# MB_ANALOG.net
KiCad netlist of a schematic drawn in Altium Designer
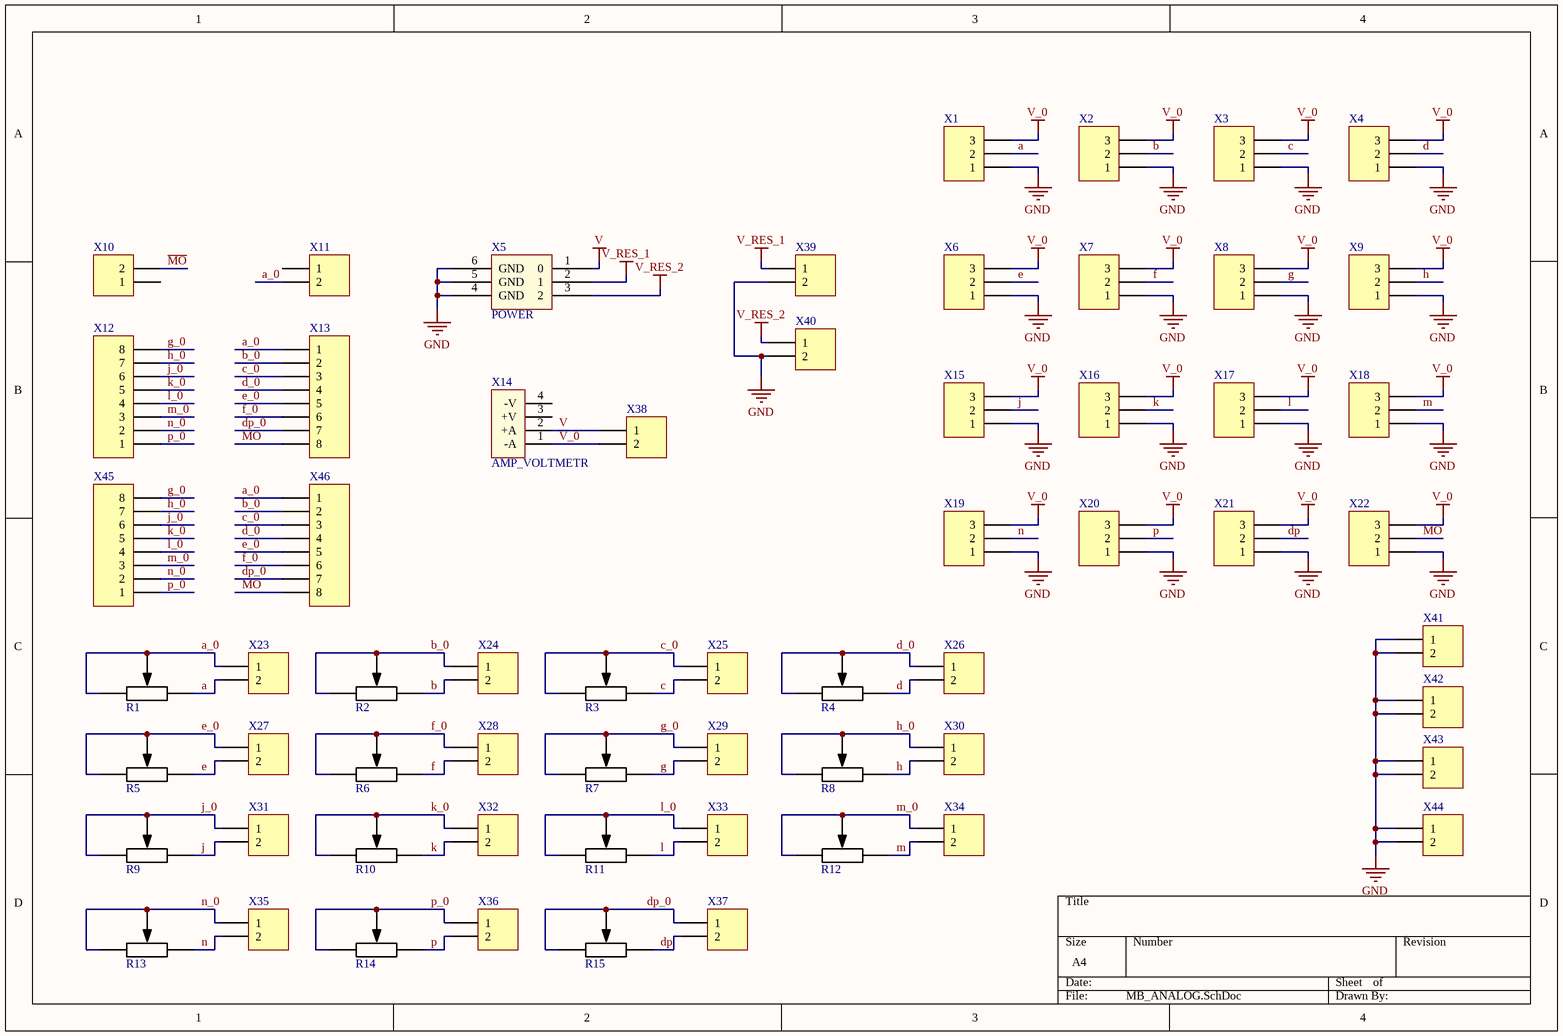
[diagram p0: MB_ANALOG.SchDoc]

(export (version "E")
  (design (tool "Eeschema 10.0.6"))
  (components
    (comp (ref "R1")
      (value "RES 3266W")
      (footprint "RES 3266W")
      (libsource (lib "msp_SchLib") (part "RES 3266W"))
    )
    (comp (ref "R2")
      (value "RES 3266W")
      (footprint "RES 3266W")
      (libsource (lib "msp_SchLib") (part "RES 3266W"))
    )
    (comp (ref "R3")
      (value "RES 3266W")
      (footprint "RES 3266W")
      (libsource (lib "msp_SchLib") (part "RES 3266W"))
    )
    (comp (ref "R4")
      (value "RES 3266W")
      (footprint "RES 3266W")
      (libsource (lib "msp_SchLib") (part "RES 3266W"))
    )
    (comp (ref "R5")
      (value "RES 3266W")
      (footprint "RES 3266W")
      (libsource (lib "msp_SchLib") (part "RES 3266W"))
    )
    (comp (ref "R6")
      (value "RES 3266W")
      (footprint "RES 3266W")
      (libsource (lib "msp_SchLib") (part "RES 3266W"))
    )
    (comp (ref "R7")
      (value "RES 3266W")
      (footprint "RES 3266W")
      (libsource (lib "msp_SchLib") (part "RES 3266W"))
    )
    (comp (ref "R8")
      (value "RES 3266W")
      (footprint "RES 3266W")
      (libsource (lib "msp_SchLib") (part "RES 3266W"))
    )
    (comp (ref "R9")
      (value "RES 3266W")
      (footprint "RES 3266W")
      (libsource (lib "msp_SchLib") (part "RES 3266W"))
    )
    (comp (ref "R10")
      (value "RES 3266W")
      (footprint "RES 3266W")
      (libsource (lib "msp_SchLib") (part "RES 3266W"))
    )
    (comp (ref "R11")
      (value "RES 3266W")
      (footprint "RES 3266W")
      (libsource (lib "msp_SchLib") (part "RES 3266W"))
    )
    (comp (ref "R12")
      (value "RES 3266W")
      (footprint "RES 3266W")
      (libsource (lib "msp_SchLib") (part "RES 3266W"))
    )
    (comp (ref "R13")
      (value "RES 3266W")
      (footprint "RES 3266W")
      (libsource (lib "msp_SchLib") (part "RES 3266W"))
    )
    (comp (ref "R14")
      (value "RES 3266W")
      (footprint "RES 3266W")
      (libsource (lib "msp_SchLib") (part "RES 3266W"))
    )
    (comp (ref "R15")
      (value "RES 3266W")
      (footprint "RES 3266W")
      (libsource (lib "msp_SchLib") (part "RES 3266W"))
    )
    (comp (ref "X1")
      (value "Header 3")
      (footprint "HDR1X3")
      (description "Header, 3-Pin")
      (fields (field (name "PUBLISHER") "Altium Limited"))
      (libsource (lib "Miscellaneous Connectors") (part "Header 3"))
    )
    (comp (ref "X2")
      (value "Header 3")
      (footprint "HDR1X3")
      (description "Header, 3-Pin")
      (fields (field (name "PUBLISHER") "Altium Limited"))
      (libsource (lib "Miscellaneous Connectors") (part "Header 3"))
    )
    (comp (ref "X3")
      (value "Header 3")
      (footprint "HDR1X3")
      (description "Header, 3-Pin")
      (fields (field (name "PUBLISHER") "Altium Limited"))
      (libsource (lib "Miscellaneous Connectors") (part "Header 3"))
    )
    (comp (ref "X4")
      (value "Header 3")
      (footprint "HDR1X3")
      (description "Header, 3-Pin")
      (fields (field (name "PUBLISHER") "Altium Limited"))
      (libsource (lib "Miscellaneous Connectors") (part "Header 3"))
    )
    (comp (ref "X5") (value "POWER") (footprint "POWER") (libsource (lib "msp_SchLib") (part "POWER")))
    (comp (ref "X6")
      (value "Header 3")
      (footprint "HDR1X3")
      (description "Header, 3-Pin")
      (fields (field (name "PUBLISHER") "Altium Limited"))
      (libsource (lib "Miscellaneous Connectors") (part "Header 3"))
    )
    (comp (ref "X7")
      (value "Header 3")
      (footprint "HDR1X3")
      (description "Header, 3-Pin")
      (fields (field (name "PUBLISHER") "Altium Limited"))
      (libsource (lib "Miscellaneous Connectors") (part "Header 3"))
    )
    (comp (ref "X8")
      (value "Header 3")
      (footprint "HDR1X3")
      (description "Header, 3-Pin")
      (fields (field (name "PUBLISHER") "Altium Limited"))
      (libsource (lib "Miscellaneous Connectors") (part "Header 3"))
    )
    (comp (ref "X9")
      (value "Header 3")
      (footprint "HDR1X3")
      (description "Header, 3-Pin")
      (fields (field (name "PUBLISHER") "Altium Limited"))
      (libsource (lib "Miscellaneous Connectors") (part "Header 3"))
    )
    (comp (ref "X10")
      (value "Header 2")
      (footprint "HDR1X2")
      (description "Header, 2-Pin")
      (fields (field (name "PUBLISHER") "Altium Limited"))
      (libsource (lib "") (part "Header 2_1"))
    )
    (comp (ref "X11")
      (value "Header 2")
      (footprint "HDR1X2")
      (description "Header, 2-Pin")
      (fields (field (name "PUBLISHER") "Altium Limited"))
      (libsource (lib "Miscellaneous Connectors") (part "Header 2"))
    )
    (comp (ref "X12")
      (value "Header 8")
      (footprint "HDR1X8")
      (description "Header, 8-Pin")
      (fields (field (name "PUBLISHER") "Altium Limited"))
      (libsource (lib "Miscellaneous Connectors") (part "Header 8"))
    )
    (comp (ref "X13")
      (value "Header 8")
      (footprint "HDR1X8")
      (description "Header, 8-Pin")
      (fields (field (name "PUBLISHER") "Altium Limited"))
      (libsource (lib "") (part "Header 8_1"))
    )
    (comp (ref "X14")
      (value "AMP_VOLTMETR")
      (footprint "AMP_VOLTMETR")
      (libsource (lib "msp_SchLib") (part "AMP_VOLTMETR"))
    )
    (comp (ref "X15")
      (value "Header 3")
      (footprint "HDR1X3")
      (description "Header, 3-Pin")
      (fields (field (name "PUBLISHER") "Altium Limited"))
      (libsource (lib "Miscellaneous Connectors") (part "Header 3"))
    )
    (comp (ref "X16")
      (value "Header 3")
      (footprint "HDR1X3")
      (description "Header, 3-Pin")
      (fields (field (name "PUBLISHER") "Altium Limited"))
      (libsource (lib "Miscellaneous Connectors") (part "Header 3"))
    )
    (comp (ref "X17")
      (value "Header 3")
      (footprint "HDR1X3")
      (description "Header, 3-Pin")
      (fields (field (name "PUBLISHER") "Altium Limited"))
      (libsource (lib "Miscellaneous Connectors") (part "Header 3"))
    )
    (comp (ref "X18")
      (value "Header 3")
      (footprint "HDR1X3")
      (description "Header, 3-Pin")
      (fields (field (name "PUBLISHER") "Altium Limited"))
      (libsource (lib "Miscellaneous Connectors") (part "Header 3"))
    )
    (comp (ref "X19")
      (value "Header 3")
      (footprint "HDR1X3")
      (description "Header, 3-Pin")
      (fields (field (name "PUBLISHER") "Altium Limited"))
      (libsource (lib "Miscellaneous Connectors") (part "Header 3"))
    )
    (comp (ref "X20")
      (value "Header 3")
      (footprint "HDR1X3")
      (description "Header, 3-Pin")
      (fields (field (name "PUBLISHER") "Altium Limited"))
      (libsource (lib "Miscellaneous Connectors") (part "Header 3"))
    )
    (comp (ref "X21")
      (value "Header 3")
      (footprint "HDR1X3")
      (description "Header, 3-Pin")
      (fields (field (name "PUBLISHER") "Altium Limited"))
      (libsource (lib "Miscellaneous Connectors") (part "Header 3"))
    )
    (comp (ref "X22")
      (value "Header 3")
      (footprint "HDR1X3")
      (description "Header, 3-Pin")
      (fields (field (name "PUBLISHER") "Altium Limited"))
      (libsource (lib "Miscellaneous Connectors") (part "Header 3"))
    )
    (comp (ref "X23")
      (value "Header 2")
      (footprint "HDR1X2")
      (description "Header, 2-Pin")
      (fields (field (name "PUBLISHER") "Altium Limited"))
      (libsource (lib "Miscellaneous Connectors") (part "Header 2"))
    )
    (comp (ref "X24")
      (value "Header 2")
      (footprint "HDR1X2")
      (description "Header, 2-Pin")
      (fields (field (name "PUBLISHER") "Altium Limited"))
      (libsource (lib "Miscellaneous Connectors") (part "Header 2"))
    )
    (comp (ref "X25")
      (value "Header 2")
      (footprint "HDR1X2")
      (description "Header, 2-Pin")
      (fields (field (name "PUBLISHER") "Altium Limited"))
      (libsource (lib "Miscellaneous Connectors") (part "Header 2"))
    )
    (comp (ref "X26")
      (value "Header 2")
      (footprint "HDR1X2")
      (description "Header, 2-Pin")
      (fields (field (name "PUBLISHER") "Altium Limited"))
      (libsource (lib "Miscellaneous Connectors") (part "Header 2"))
    )
    (comp (ref "X27")
      (value "Header 2")
      (footprint "HDR1X2")
      (description "Header, 2-Pin")
      (fields (field (name "PUBLISHER") "Altium Limited"))
      (libsource (lib "Miscellaneous Connectors") (part "Header 2"))
    )
    (comp (ref "X28")
      (value "Header 2")
      (footprint "HDR1X2")
      (description "Header, 2-Pin")
      (fields (field (name "PUBLISHER") "Altium Limited"))
      (libsource (lib "Miscellaneous Connectors") (part "Header 2"))
    )
    (comp (ref "X29")
      (value "Header 2")
      (footprint "HDR1X2")
      (description "Header, 2-Pin")
      (fields (field (name "PUBLISHER") "Altium Limited"))
      (libsource (lib "Miscellaneous Connectors") (part "Header 2"))
    )
    (comp (ref "X30")
      (value "Header 2")
      (footprint "HDR1X2")
      (description "Header, 2-Pin")
      (fields (field (name "PUBLISHER") "Altium Limited"))
      (libsource (lib "Miscellaneous Connectors") (part "Header 2"))
    )
    (comp (ref "X31")
      (value "Header 2")
      (footprint "HDR1X2")
      (description "Header, 2-Pin")
      (fields (field (name "PUBLISHER") "Altium Limited"))
      (libsource (lib "Miscellaneous Connectors") (part "Header 2"))
    )
    (comp (ref "X32")
      (value "Header 2")
      (footprint "HDR1X2")
      (description "Header, 2-Pin")
      (fields (field (name "PUBLISHER") "Altium Limited"))
      (libsource (lib "Miscellaneous Connectors") (part "Header 2"))
    )
    (comp (ref "X33")
      (value "Header 2")
      (footprint "HDR1X2")
      (description "Header, 2-Pin")
      (fields (field (name "PUBLISHER") "Altium Limited"))
      (libsource (lib "Miscellaneous Connectors") (part "Header 2"))
    )
    (comp (ref "X34")
      (value "Header 2")
      (footprint "HDR1X2")
      (description "Header, 2-Pin")
      (fields (field (name "PUBLISHER") "Altium Limited"))
      (libsource (lib "Miscellaneous Connectors") (part "Header 2"))
    )
    (comp (ref "X35")
      (value "Header 2")
      (footprint "HDR1X2")
      (description "Header, 2-Pin")
      (fields (field (name "PUBLISHER") "Altium Limited"))
      (libsource (lib "Miscellaneous Connectors") (part "Header 2"))
    )
    (comp (ref "X36")
      (value "Header 2")
      (footprint "HDR1X2")
      (description "Header, 2-Pin")
      (fields (field (name "PUBLISHER") "Altium Limited"))
      (libsource (lib "Miscellaneous Connectors") (part "Header 2"))
    )
    (comp (ref "X37")
      (value "Header 2")
      (footprint "HDR1X2")
      (description "Header, 2-Pin")
      (fields (field (name "PUBLISHER") "Altium Limited"))
      (libsource (lib "Miscellaneous Connectors") (part "Header 2"))
    )
    (comp (ref "X38")
      (value "Header 2")
      (footprint "HDR1X2")
      (description "Header, 2-Pin")
      (fields (field (name "PUBLISHER") "Altium Limited"))
      (libsource (lib "Miscellaneous Connectors") (part "Header 2"))
    )
    (comp (ref "X39")
      (value "Header 2")
      (footprint "HDR1X2")
      (description "Header, 2-Pin")
      (fields (field (name "PUBLISHER") "Altium Limited"))
      (libsource (lib "Miscellaneous Connectors") (part "Header 2"))
    )
    (comp (ref "X40")
      (value "Header 2")
      (footprint "HDR1X2")
      (description "Header, 2-Pin")
      (fields (field (name "PUBLISHER") "Altium Limited"))
      (libsource (lib "Miscellaneous Connectors") (part "Header 2"))
    )
    (comp (ref "X41")
      (value "Header 2")
      (footprint "HDR1X2")
      (description "Header, 2-Pin")
      (fields (field (name "PUBLISHER") "Altium Limited"))
      (libsource (lib "Miscellaneous Connectors") (part "Header 2"))
    )
    (comp (ref "X42")
      (value "Header 2")
      (footprint "HDR1X2")
      (description "Header, 2-Pin")
      (fields (field (name "PUBLISHER") "Altium Limited"))
      (libsource (lib "Miscellaneous Connectors") (part "Header 2"))
    )
    (comp (ref "X43")
      (value "Header 2")
      (footprint "HDR1X2")
      (description "Header, 2-Pin")
      (fields (field (name "PUBLISHER") "Altium Limited"))
      (libsource (lib "Miscellaneous Connectors") (part "Header 2"))
    )
    (comp (ref "X44")
      (value "Header 2")
      (footprint "HDR1X2")
      (description "Header, 2-Pin")
      (fields (field (name "PUBLISHER") "Altium Limited"))
      (libsource (lib "Miscellaneous Connectors") (part "Header 2"))
    )
    (comp (ref "X45")
      (value "Header 8")
      (footprint "HDR1X8")
      (description "Header, 8-Pin")
      (fields (field (name "PUBLISHER") "Altium Limited"))
      (libsource (lib "Miscellaneous Connectors") (part "Header 8"))
    )
    (comp (ref "X46")
      (value "Header 8")
      (footprint "HDR1X8")
      (description "Header, 8-Pin")
      (fields (field (name "PUBLISHER") "Altium Limited"))
      (libsource (lib "") (part "Header 8_1"))
    )
  )
  (nets
    (net (code "1") (name "/a") (class "Default")
      (node (ref "R1") (pin "3") (pinfunction "3_3") (pintype "passive"))
      (node (ref "X1") (pin "2") (pinfunction "2_2") (pintype "passive"))
      (node (ref "X23") (pin "2") (pinfunction "2_2") (pintype "passive"))
    )
    (net (code "2") (name "/a_0") (class "Default")
      (node (ref "R1") (pin "1") (pinfunction "1_1") (pintype "passive"))
      (node (ref "R1") (pin "2") (pinfunction "2_2") (pintype "passive"))
      (node (ref "X11") (pin "2") (pinfunction "2_2") (pintype "passive"))
      (node (ref "X13") (pin "1") (pinfunction "1_1") (pintype "passive"))
      (node (ref "X23") (pin "1") (pinfunction "1_1") (pintype "passive"))
      (node (ref "X46") (pin "1") (pinfunction "1_1") (pintype "passive"))
    )
    (net (code "3") (name "/b") (class "Default")
      (node (ref "R2") (pin "3") (pinfunction "3_3") (pintype "passive"))
      (node (ref "X2") (pin "2") (pinfunction "2_2") (pintype "passive"))
      (node (ref "X24") (pin "2") (pinfunction "2_2") (pintype "passive"))
    )
    (net (code "4") (name "/b_0") (class "Default")
      (node (ref "R2") (pin "1") (pinfunction "1_1") (pintype "passive"))
      (node (ref "R2") (pin "2") (pinfunction "2_2") (pintype "passive"))
      (node (ref "X13") (pin "2") (pinfunction "2_2") (pintype "passive"))
      (node (ref "X24") (pin "1") (pinfunction "1_1") (pintype "passive"))
      (node (ref "X46") (pin "2") (pinfunction "2_2") (pintype "passive"))
    )
    (net (code "5") (name "/c") (class "Default")
      (node (ref "R3") (pin "3") (pinfunction "3_3") (pintype "passive"))
      (node (ref "X25") (pin "2") (pinfunction "2_2") (pintype "passive"))
      (node (ref "X3") (pin "2") (pinfunction "2_2") (pintype "passive"))
    )
    (net (code "6") (name "/c_0") (class "Default")
      (node (ref "R3") (pin "1") (pinfunction "1_1") (pintype "passive"))
      (node (ref "R3") (pin "2") (pinfunction "2_2") (pintype "passive"))
      (node (ref "X13") (pin "3") (pinfunction "3_3") (pintype "passive"))
      (node (ref "X25") (pin "1") (pinfunction "1_1") (pintype "passive"))
      (node (ref "X46") (pin "3") (pinfunction "3_3") (pintype "passive"))
    )
    (net (code "7") (name "/d") (class "Default")
      (node (ref "R4") (pin "3") (pinfunction "3_3") (pintype "passive"))
      (node (ref "X26") (pin "2") (pinfunction "2_2") (pintype "passive"))
      (node (ref "X4") (pin "2") (pinfunction "2_2") (pintype "passive"))
    )
    (net (code "8") (name "/d_0") (class "Default")
      (node (ref "R4") (pin "1") (pinfunction "1_1") (pintype "passive"))
      (node (ref "R4") (pin "2") (pinfunction "2_2") (pintype "passive"))
      (node (ref "X13") (pin "4") (pinfunction "4_4") (pintype "passive"))
      (node (ref "X26") (pin "1") (pinfunction "1_1") (pintype "passive"))
      (node (ref "X46") (pin "4") (pinfunction "4_4") (pintype "passive"))
    )
    (net (code "9") (name "/dp") (class "Default")
      (node (ref "R15") (pin "3") (pinfunction "3_3") (pintype "passive"))
      (node (ref "X21") (pin "2") (pinfunction "2_2") (pintype "passive"))
      (node (ref "X37") (pin "2") (pinfunction "2_2") (pintype "passive"))
    )
    (net (code "10") (name "/dp_0") (class "Default")
      (node (ref "R15") (pin "1") (pinfunction "1_1") (pintype "passive"))
      (node (ref "R15") (pin "2") (pinfunction "2_2") (pintype "passive"))
      (node (ref "X13") (pin "7") (pinfunction "7_7") (pintype "passive"))
      (node (ref "X37") (pin "1") (pinfunction "1_1") (pintype "passive"))
      (node (ref "X46") (pin "7") (pinfunction "7_7") (pintype "passive"))
    )
    (net (code "11") (name "/e") (class "Default")
      (node (ref "R5") (pin "3") (pinfunction "3_3") (pintype "passive"))
      (node (ref "X27") (pin "2") (pinfunction "2_2") (pintype "passive"))
      (node (ref "X6") (pin "2") (pinfunction "2_2") (pintype "passive"))
    )
    (net (code "12") (name "/e_0") (class "Default")
      (node (ref "R5") (pin "1") (pinfunction "1_1") (pintype "passive"))
      (node (ref "R5") (pin "2") (pinfunction "2_2") (pintype "passive"))
      (node (ref "X13") (pin "5") (pinfunction "5_5") (pintype "passive"))
      (node (ref "X27") (pin "1") (pinfunction "1_1") (pintype "passive"))
      (node (ref "X46") (pin "5") (pinfunction "5_5") (pintype "passive"))
    )
    (net (code "13") (name "/f") (class "Default")
      (node (ref "R6") (pin "3") (pinfunction "3_3") (pintype "passive"))
      (node (ref "X28") (pin "2") (pinfunction "2_2") (pintype "passive"))
      (node (ref "X7") (pin "2") (pinfunction "2_2") (pintype "passive"))
    )
    (net (code "14") (name "/f_0") (class "Default")
      (node (ref "R6") (pin "1") (pinfunction "1_1") (pintype "passive"))
      (node (ref "R6") (pin "2") (pinfunction "2_2") (pintype "passive"))
      (node (ref "X13") (pin "6") (pinfunction "6_6") (pintype "passive"))
      (node (ref "X28") (pin "1") (pinfunction "1_1") (pintype "passive"))
      (node (ref "X46") (pin "6") (pinfunction "6_6") (pintype "passive"))
    )
    (net (code "15") (name "/g") (class "Default")
      (node (ref "R7") (pin "3") (pinfunction "3_3") (pintype "passive"))
      (node (ref "X29") (pin "2") (pinfunction "2_2") (pintype "passive"))
      (node (ref "X8") (pin "2") (pinfunction "2_2") (pintype "passive"))
    )
    (net (code "16") (name "/g_0") (class "Default")
      (node (ref "R7") (pin "1") (pinfunction "1_1") (pintype "passive"))
      (node (ref "R7") (pin "2") (pinfunction "2_2") (pintype "passive"))
      (node (ref "X12") (pin "8") (pinfunction "8_8") (pintype "passive"))
      (node (ref "X29") (pin "1") (pinfunction "1_1") (pintype "passive"))
      (node (ref "X45") (pin "8") (pinfunction "8_8") (pintype "passive"))
    )
    (net (code "17") (name "/h") (class "Default")
      (node (ref "R8") (pin "3") (pinfunction "3_3") (pintype "passive"))
      (node (ref "X30") (pin "2") (pinfunction "2_2") (pintype "passive"))
      (node (ref "X9") (pin "2") (pinfunction "2_2") (pintype "passive"))
    )
    (net (code "18") (name "/h_0") (class "Default")
      (node (ref "R8") (pin "1") (pinfunction "1_1") (pintype "passive"))
      (node (ref "R8") (pin "2") (pinfunction "2_2") (pintype "passive"))
      (node (ref "X12") (pin "7") (pinfunction "7_7") (pintype "passive"))
      (node (ref "X30") (pin "1") (pinfunction "1_1") (pintype "passive"))
      (node (ref "X45") (pin "7") (pinfunction "7_7") (pintype "passive"))
    )
    (net (code "19") (name "/j") (class "Default")
      (node (ref "R9") (pin "3") (pinfunction "3_3") (pintype "passive"))
      (node (ref "X15") (pin "2") (pinfunction "2_2") (pintype "passive"))
      (node (ref "X31") (pin "2") (pinfunction "2_2") (pintype "passive"))
    )
    (net (code "20") (name "/j_0") (class "Default")
      (node (ref "R9") (pin "1") (pinfunction "1_1") (pintype "passive"))
      (node (ref "R9") (pin "2") (pinfunction "2_2") (pintype "passive"))
      (node (ref "X12") (pin "6") (pinfunction "6_6") (pintype "passive"))
      (node (ref "X31") (pin "1") (pinfunction "1_1") (pintype "passive"))
      (node (ref "X45") (pin "6") (pinfunction "6_6") (pintype "passive"))
    )
    (net (code "21") (name "/k") (class "Default")
      (node (ref "R10") (pin "3") (pinfunction "3_3") (pintype "passive"))
      (node (ref "X16") (pin "2") (pinfunction "2_2") (pintype "passive"))
      (node (ref "X32") (pin "2") (pinfunction "2_2") (pintype "passive"))
    )
    (net (code "22") (name "/k_0") (class "Default")
      (node (ref "R10") (pin "1") (pinfunction "1_1") (pintype "passive"))
      (node (ref "R10") (pin "2") (pinfunction "2_2") (pintype "passive"))
      (node (ref "X12") (pin "5") (pinfunction "5_5") (pintype "passive"))
      (node (ref "X32") (pin "1") (pinfunction "1_1") (pintype "passive"))
      (node (ref "X45") (pin "5") (pinfunction "5_5") (pintype "passive"))
    )
    (net (code "23") (name "/l") (class "Default")
      (node (ref "R11") (pin "3") (pinfunction "3_3") (pintype "passive"))
      (node (ref "X17") (pin "2") (pinfunction "2_2") (pintype "passive"))
      (node (ref "X33") (pin "2") (pinfunction "2_2") (pintype "passive"))
    )
    (net (code "24") (name "/l_0") (class "Default")
      (node (ref "R11") (pin "1") (pinfunction "1_1") (pintype "passive"))
      (node (ref "R11") (pin "2") (pinfunction "2_2") (pintype "passive"))
      (node (ref "X12") (pin "4") (pinfunction "4_4") (pintype "passive"))
      (node (ref "X33") (pin "1") (pinfunction "1_1") (pintype "passive"))
      (node (ref "X45") (pin "4") (pinfunction "4_4") (pintype "passive"))
    )
    (net (code "25") (name "/m") (class "Default")
      (node (ref "R12") (pin "3") (pinfunction "3_3") (pintype "passive"))
      (node (ref "X18") (pin "2") (pinfunction "2_2") (pintype "passive"))
      (node (ref "X34") (pin "2") (pinfunction "2_2") (pintype "passive"))
    )
    (net (code "26") (name "/m_0") (class "Default")
      (node (ref "R12") (pin "1") (pinfunction "1_1") (pintype "passive"))
      (node (ref "R12") (pin "2") (pinfunction "2_2") (pintype "passive"))
      (node (ref "X12") (pin "3") (pinfunction "3_3") (pintype "passive"))
      (node (ref "X34") (pin "1") (pinfunction "1_1") (pintype "passive"))
      (node (ref "X45") (pin "3") (pinfunction "3_3") (pintype "passive"))
    )
    (net (code "27") (name "/n") (class "Default")
      (node (ref "R13") (pin "3") (pinfunction "3_3") (pintype "passive"))
      (node (ref "X19") (pin "2") (pinfunction "2_2") (pintype "passive"))
      (node (ref "X35") (pin "2") (pinfunction "2_2") (pintype "passive"))
    )
    (net (code "28") (name "/n_0") (class "Default")
      (node (ref "R13") (pin "1") (pinfunction "1_1") (pintype "passive"))
      (node (ref "R13") (pin "2") (pinfunction "2_2") (pintype "passive"))
      (node (ref "X12") (pin "2") (pinfunction "2_2") (pintype "passive"))
      (node (ref "X35") (pin "1") (pinfunction "1_1") (pintype "passive"))
      (node (ref "X45") (pin "2") (pinfunction "2_2") (pintype "passive"))
    )
    (net (code "29") (name "/p") (class "Default")
      (node (ref "R14") (pin "3") (pinfunction "3_3") (pintype "passive"))
      (node (ref "X20") (pin "2") (pinfunction "2_2") (pintype "passive"))
      (node (ref "X36") (pin "2") (pinfunction "2_2") (pintype "passive"))
    )
    (net (code "30") (name "/p_0") (class "Default")
      (node (ref "R14") (pin "1") (pinfunction "1_1") (pintype "passive"))
      (node (ref "R14") (pin "2") (pinfunction "2_2") (pintype "passive"))
      (node (ref "X12") (pin "1") (pinfunction "1_1") (pintype "passive"))
      (node (ref "X36") (pin "1") (pinfunction "1_1") (pintype "passive"))
      (node (ref "X45") (pin "1") (pinfunction "1_1") (pintype "passive"))
    )
    (net (code "31") (name "/~{MO}") (class "Default")
      (node (ref "X10") (pin "2") (pinfunction "2_2") (pintype "passive"))
      (node (ref "X13") (pin "8") (pinfunction "8_8") (pintype "passive"))
      (node (ref "X22") (pin "2") (pinfunction "2_2") (pintype "passive"))
      (node (ref "X46") (pin "8") (pinfunction "8_8") (pintype "passive"))
    )
    (net (code "32") (name "GND") (class "Default")
      (node (ref "X1") (pin "1") (pinfunction "1_1") (pintype "passive"))
      (node (ref "X15") (pin "1") (pinfunction "1_1") (pintype "passive"))
      (node (ref "X16") (pin "1") (pinfunction "1_1") (pintype "passive"))
      (node (ref "X17") (pin "1") (pinfunction "1_1") (pintype "passive"))
      (node (ref "X18") (pin "1") (pinfunction "1_1") (pintype "passive"))
      (node (ref "X19") (pin "1") (pinfunction "1_1") (pintype "passive"))
      (node (ref "X2") (pin "1") (pinfunction "1_1") (pintype "passive"))
      (node (ref "X20") (pin "1") (pinfunction "1_1") (pintype "passive"))
      (node (ref "X21") (pin "1") (pinfunction "1_1") (pintype "passive"))
      (node (ref "X22") (pin "1") (pinfunction "1_1") (pintype "passive"))
      (node (ref "X3") (pin "1") (pinfunction "1_1") (pintype "passive"))
      (node (ref "X39") (pin "2") (pinfunction "2_2") (pintype "passive"))
      (node (ref "X4") (pin "1") (pinfunction "1_1") (pintype "passive"))
      (node (ref "X40") (pin "2") (pinfunction "2_2") (pintype "passive"))
      (node (ref "X41") (pin "1") (pinfunction "1_1") (pintype "passive"))
      (node (ref "X41") (pin "2") (pinfunction "2_2") (pintype "passive"))
      (node (ref "X42") (pin "1") (pinfunction "1_1") (pintype "passive"))
      (node (ref "X42") (pin "2") (pinfunction "2_2") (pintype "passive"))
      (node (ref "X43") (pin "1") (pinfunction "1_1") (pintype "passive"))
      (node (ref "X43") (pin "2") (pinfunction "2_2") (pintype "passive"))
      (node (ref "X44") (pin "1") (pinfunction "1_1") (pintype "passive"))
      (node (ref "X44") (pin "2") (pinfunction "2_2") (pintype "passive"))
      (node (ref "X5") (pin "4") (pinfunction "GND_4") (pintype "passive"))
      (node (ref "X5") (pin "5") (pinfunction "GND_5") (pintype "passive"))
      (node (ref "X5") (pin "6") (pinfunction "GND_6") (pintype "passive"))
      (node (ref "X6") (pin "1") (pinfunction "1_1") (pintype "passive"))
      (node (ref "X7") (pin "1") (pinfunction "1_1") (pintype "passive"))
      (node (ref "X8") (pin "1") (pinfunction "1_1") (pintype "passive"))
      (node (ref "X9") (pin "1") (pinfunction "1_1") (pintype "passive"))
    )
    (net (code "33") (name "V") (class "Default")
      (node (ref "X14") (pin "2") (pinfunction "+A_2") (pintype "passive"))
      (node (ref "X38") (pin "1") (pinfunction "1_1") (pintype "passive"))
      (node (ref "X5") (pin "1") (pinfunction "0_1") (pintype "passive"))
    )
    (net (code "34") (name "V_0") (class "Default")
      (node (ref "X1") (pin "3") (pinfunction "3_3") (pintype "passive"))
      (node (ref "X14") (pin "1") (pinfunction "-A_1") (pintype "passive"))
      (node (ref "X15") (pin "3") (pinfunction "3_3") (pintype "passive"))
      (node (ref "X16") (pin "3") (pinfunction "3_3") (pintype "passive"))
      (node (ref "X17") (pin "3") (pinfunction "3_3") (pintype "passive"))
      (node (ref "X18") (pin "3") (pinfunction "3_3") (pintype "passive"))
      (node (ref "X19") (pin "3") (pinfunction "3_3") (pintype "passive"))
      (node (ref "X2") (pin "3") (pinfunction "3_3") (pintype "passive"))
      (node (ref "X20") (pin "3") (pinfunction "3_3") (pintype "passive"))
      (node (ref "X21") (pin "3") (pinfunction "3_3") (pintype "passive"))
      (node (ref "X22") (pin "3") (pinfunction "3_3") (pintype "passive"))
      (node (ref "X3") (pin "3") (pinfunction "3_3") (pintype "passive"))
      (node (ref "X38") (pin "2") (pinfunction "2_2") (pintype "passive"))
      (node (ref "X4") (pin "3") (pinfunction "3_3") (pintype "passive"))
      (node (ref "X6") (pin "3") (pinfunction "3_3") (pintype "passive"))
      (node (ref "X7") (pin "3") (pinfunction "3_3") (pintype "passive"))
      (node (ref "X8") (pin "3") (pinfunction "3_3") (pintype "passive"))
      (node (ref "X9") (pin "3") (pinfunction "3_3") (pintype "passive"))
    )
    (net (code "35") (name "V_RES_1") (class "Default")
      (node (ref "X39") (pin "1") (pinfunction "1_1") (pintype "passive"))
      (node (ref "X5") (pin "2") (pinfunction "1_2") (pintype "passive"))
    )
    (net (code "36") (name "V_RES_2") (class "Default")
      (node (ref "X40") (pin "1") (pinfunction "1_1") (pintype "passive"))
      (node (ref "X5") (pin "3") (pinfunction "2_3") (pintype "passive"))
    )
    (net (code "37") (name "unconnected-(X10-Pad1)") (class "Default")
      (node (ref "X10") (pin "1") (pinfunction "1_1") (pintype "passive"))
    )
    (net (code "38") (name "unconnected-(X11-Pad1)") (class "Default")
      (node (ref "X11") (pin "1") (pinfunction "1_1") (pintype "passive"))
    )
    (net (code "39") (name "unconnected-(X14-+V-Pad3)") (class "Default")
      (node (ref "X14") (pin "3") (pinfunction "+V_3") (pintype "passive"))
    )
    (net (code "40") (name "unconnected-(X14--V-Pad4)") (class "Default")
      (node (ref "X14") (pin "4") (pinfunction "-V_4") (pintype "passive"))
    )
  )
)
